# receiver.net
KiCad netlist of a schematic drawn in EAGLE
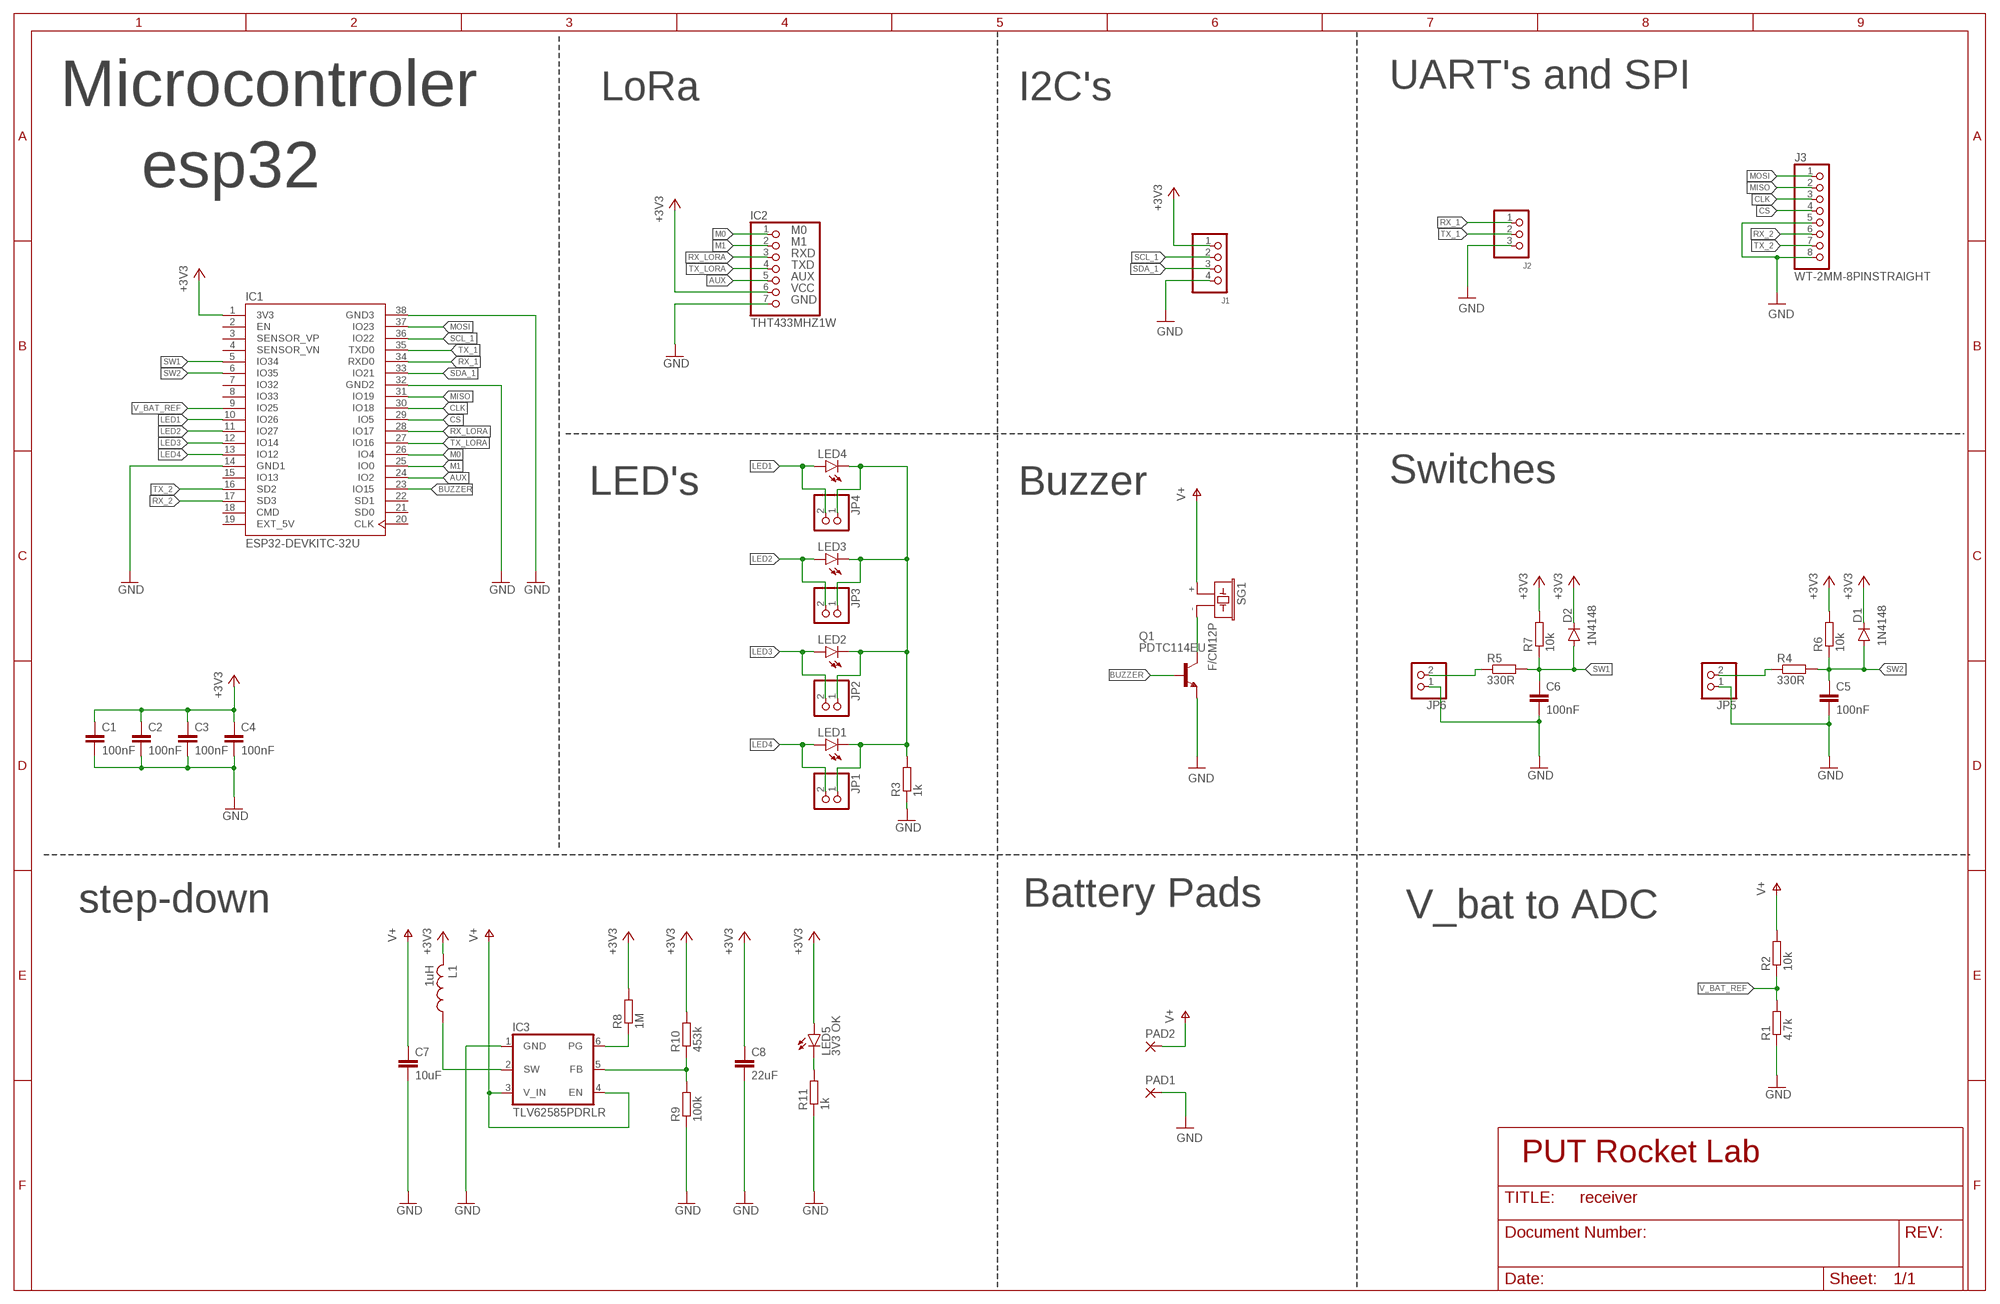
[diagram p0: schematic, sheet 1]

(export (version "E")
  (design (tool "Eeschema 10.0.6"))
  (components
    (comp (ref "C1")
      (value "100nF")
      (footprint "eagle-import:C0805")
      (libsource (lib "eagle-import") (part "C-EUC0805"))
    )
    (comp (ref "C2")
      (value "100nF")
      (footprint "eagle-import:C0805")
      (libsource (lib "eagle-import") (part "C-EUC0805"))
    )
    (comp (ref "C3")
      (value "100nF")
      (footprint "eagle-import:C0805")
      (libsource (lib "eagle-import") (part "C-EUC0805"))
    )
    (comp (ref "C4")
      (value "100nF")
      (footprint "eagle-import:C0805")
      (libsource (lib "eagle-import") (part "C-EUC0805"))
    )
    (comp (ref "C5")
      (value "100nF")
      (footprint "eagle-import:C0805")
      (libsource (lib "eagle-import") (part "rcl_334_C-EUC0805"))
    )
    (comp (ref "C6")
      (value "100nF")
      (footprint "eagle-import:C0805")
      (libsource (lib "eagle-import") (part "rcl_334_C-EUC0805"))
    )
    (comp (ref "C7")
      (value "10uF")
      (footprint "eagle-import:C0805")
      (libsource (lib "eagle-import") (part "C-EUC0805"))
    )
    (comp (ref "C8")
      (value "22uF")
      (footprint "eagle-import:C0805")
      (libsource (lib "eagle-import") (part "C-EUC0805"))
    )
    (comp (ref "D1")
      (value "1N4148")
      (footprint "eagle-import:SOD80C")
      (libsource (lib "eagle-import") (part "DIODE-SOD80C"))
    )
    (comp (ref "D2")
      (value "1N4148")
      (footprint "eagle-import:SOD80C")
      (libsource (lib "eagle-import") (part "DIODE-SOD80C"))
    )
    (comp (ref "IC1")
      (value "ESP32-DEVKITC-32U")
      (footprint "eagle-import:MODULE_ESP32-DEVKITC-32U")
      (fields (field (name "MF") "Espressif Systems"))
      (libsource (lib "eagle-import") (part "ESP32-DEVKITC-32U"))
    )
    (comp (ref "IC2")
      (value "THT433MHZ1W")
      (footprint "eagle-import:E32M1000")
      (libsource (lib "eagle-import") (part "THT433MHZ1W"))
    )
    (comp (ref "IC3")
      (value "TLV62585PDRLR")
      (footprint "eagle-import:SOT563")
      (libsource (lib "eagle-import") (part "TLV62585PDRLR"))
    )
    (comp (ref "J1")
      (value "WT-2MM-4PINSTRAIGHT")
      (footprint "eagle-import:W_TYPE_2MM_4_N")
      (libsource (lib "eagle-import") (part "WT-2MM-4PINSTRAIGHT"))
    )
    (comp (ref "J2")
      (value "WT-2MM-3PINSTRAIGHT")
      (footprint "eagle-import:W_TYPE_2MM_3_N")
      (libsource (lib "eagle-import") (part "WT-2MM-3PINSTRAIGHT"))
    )
    (comp (ref "J3")
      (value "WT-2MM-8PINSTRAIGHT")
      (footprint "eagle-import:W_TYPE_2MM_8_N")
      (libsource (lib "eagle-import") (part "WT-2MM-8PINSTRAIGHT"))
    )
    (comp (ref "JP1")
      (value "PINHD-1X2")
      (footprint "eagle-import:1X02")
      (libsource (lib "eagle-import") (part "PINHD-1X2"))
    )
    (comp (ref "JP2")
      (value "PINHD-1X2")
      (footprint "eagle-import:1X02")
      (libsource (lib "eagle-import") (part "PINHD-1X2"))
    )
    (comp (ref "JP3")
      (value "PINHD-1X2")
      (footprint "eagle-import:1X02")
      (libsource (lib "eagle-import") (part "PINHD-1X2"))
    )
    (comp (ref "JP4")
      (value "PINHD-1X2")
      (footprint "eagle-import:1X02")
      (libsource (lib "eagle-import") (part "PINHD-1X2"))
    )
    (comp (ref "JP5")
      (value "PINHD-1X2")
      (footprint "eagle-import:1X02")
      (libsource (lib "eagle-import") (part "PINHD-1X2"))
    )
    (comp (ref "JP6")
      (value "PINHD-1X2")
      (footprint "eagle-import:1X02")
      (libsource (lib "eagle-import") (part "PINHD-1X2"))
    )
    (comp (ref "L1")
      (value "1uH")
      (footprint "eagle-import:L5650M")
      (libsource (lib "eagle-import") (part "L-USL5650M"))
    )
    (comp (ref "LED1")
      (value "LEDCHIPLED_0805")
      (footprint "eagle-import:CHIPLED_0805")
      (libsource (lib "eagle-import") (part "LEDCHIPLED_0805"))
    )
    (comp (ref "LED2")
      (value "LEDCHIPLED_0805")
      (footprint "eagle-import:CHIPLED_0805")
      (libsource (lib "eagle-import") (part "LEDCHIPLED_0805"))
    )
    (comp (ref "LED3")
      (value "LEDCHIPLED_0805")
      (footprint "eagle-import:CHIPLED_0805")
      (libsource (lib "eagle-import") (part "LEDCHIPLED_0805"))
    )
    (comp (ref "LED4")
      (value "LEDCHIPLED_0805")
      (footprint "eagle-import:CHIPLED_0805")
      (libsource (lib "eagle-import") (part "LEDCHIPLED_0805"))
    )
    (comp (ref "LED5")
      (value "3V3 OK")
      (footprint "eagle-import:CHIPLED_0805")
      (libsource (lib "eagle-import") (part "LEDCHIPLED_0805"))
    )
    (comp (ref "PAD1")
      (value "WIREPAD2,54/1,1")
      (footprint "eagle-import:2,54_1,1")
      (libsource (lib "eagle-import") (part "WIREPAD2,54/1,1"))
    )
    (comp (ref "PAD2")
      (value "WIREPAD2,54/1,1")
      (footprint "eagle-import:2,54_1,1")
      (libsource (lib "eagle-import") (part "WIREPAD2,54/1,1"))
    )
    (comp (ref "Q1")
      (value "PDTC114EU")
      (footprint "eagle-import:SOT23")
      (libsource (lib "eagle-import") (part "BC846SMDA"))
    )
    (comp (ref "R1")
      (value "4.7k")
      (footprint "eagle-import:R0805")
      (libsource (lib "eagle-import") (part "R-EU_R0805"))
    )
    (comp (ref "R2")
      (value "10k")
      (footprint "eagle-import:R0805")
      (libsource (lib "eagle-import") (part "R-EU_R0805"))
    )
    (comp (ref "R3")
      (value "1k")
      (footprint "eagle-import:R0805")
      (libsource (lib "eagle-import") (part "R-EU_R0805"))
    )
    (comp (ref "R4")
      (value "330R")
      (footprint "eagle-import:R0805")
      (libsource (lib "eagle-import") (part "rcl_334_R-EU_R0805"))
    )
    (comp (ref "R5")
      (value "330R")
      (footprint "eagle-import:R0805")
      (libsource (lib "eagle-import") (part "rcl_334_R-EU_R0805"))
    )
    (comp (ref "R6")
      (value "10k")
      (footprint "eagle-import:R0805")
      (libsource (lib "eagle-import") (part "rcl_334_R-EU_R0805"))
    )
    (comp (ref "R7")
      (value "10k")
      (footprint "eagle-import:R0805")
      (libsource (lib "eagle-import") (part "rcl_334_R-EU_R0805"))
    )
    (comp (ref "R8")
      (value "1M")
      (footprint "eagle-import:R0805")
      (libsource (lib "eagle-import") (part "R-EU_R0805"))
    )
    (comp (ref "R9")
      (value "100k")
      (footprint "eagle-import:R0805")
      (libsource (lib "eagle-import") (part "R-EU_R0805"))
    )
    (comp (ref "R10")
      (value "453k")
      (footprint "eagle-import:R0805")
      (libsource (lib "eagle-import") (part "R-EU_R0805"))
    )
    (comp (ref "R11")
      (value "1k")
      (footprint "eagle-import:R0805")
      (libsource (lib "eagle-import") (part "R-EU_R0805"))
    )
    (comp (ref "SG1")
      (value "F/CM12P")
      (footprint "eagle-import:F_CM12P")
      (libsource (lib "eagle-import") (part "F/CM12P"))
    )
  )
  (nets
    (net (code "1") (name "+3V3") (class "Default")
      (node (ref "C1") (pin "1") (pinfunction "1_1") (pintype "passive"))
      (node (ref "C2") (pin "1") (pinfunction "1_1") (pintype "passive"))
      (node (ref "C3") (pin "1") (pinfunction "1_1") (pintype "passive"))
      (node (ref "C4") (pin "1") (pinfunction "1_1") (pintype "passive"))
      (node (ref "C8") (pin "1") (pinfunction "1_1") (pintype "passive"))
      (node (ref "D1") (pin "C") (pinfunction "C_C") (pintype "passive"))
      (node (ref "D2") (pin "C") (pinfunction "C_C") (pintype "passive"))
      (node (ref "IC1") (pin "1") (pinfunction "3V3_1") (pintype "power_in"))
      (node (ref "IC2") (pin "6") (pinfunction "VCC_6") (pintype "passive"))
      (node (ref "J1") (pin "1") (pinfunction "1_1") (pintype "passive"))
      (node (ref "L1") (pin "2") (pinfunction "2_2") (pintype "passive"))
      (node (ref "LED5") (pin "A") (pinfunction "A_A") (pintype "passive"))
      (node (ref "R10") (pin "2") (pinfunction "2_2") (pintype "passive"))
      (node (ref "R6") (pin "2") (pinfunction "2_2") (pintype "passive"))
      (node (ref "R7") (pin "2") (pinfunction "2_2") (pintype "passive"))
      (node (ref "R8") (pin "2") (pinfunction "2_2") (pintype "passive"))
    )
    (net (code "2") (name "/EXT_5V") (class "Default")
      (node (ref "IC1") (pin "19") (pinfunction "EXT_5V_19") (pintype "power_in"))
    )
    (net (code "3") (name "AUX") (class "Default")
      (node (ref "IC1") (pin "24") (pinfunction "IO2_24") (pintype "bidirectional"))
      (node (ref "IC2") (pin "5") (pinfunction "AUX_5") (pintype "passive"))
    )
    (net (code "4") (name "BUZZER") (class "Default")
      (node (ref "IC1") (pin "23") (pinfunction "IO15_23") (pintype "bidirectional"))
      (node (ref "Q1") (pin "1") (pinfunction "B_1") (pintype "passive"))
    )
    (net (code "5") (name "CLK") (class "Default")
      (node (ref "IC1") (pin "30") (pinfunction "IO18_30") (pintype "bidirectional"))
      (node (ref "J3") (pin "3") (pinfunction "3_3") (pintype "passive"))
    )
    (net (code "6") (name "CS") (class "Default")
      (node (ref "IC1") (pin "29") (pinfunction "IO5_29") (pintype "bidirectional"))
      (node (ref "J3") (pin "4") (pinfunction "4_4") (pintype "passive"))
    )
    (net (code "7") (name "GND") (class "Default")
      (node (ref "C1") (pin "2") (pinfunction "2_2") (pintype "passive"))
      (node (ref "C2") (pin "2") (pinfunction "2_2") (pintype "passive"))
      (node (ref "C3") (pin "2") (pinfunction "2_2") (pintype "passive"))
      (node (ref "C4") (pin "2") (pinfunction "2_2") (pintype "passive"))
      (node (ref "C5") (pin "2") (pinfunction "2_2") (pintype "passive"))
      (node (ref "C6") (pin "2") (pinfunction "2_2") (pintype "passive"))
      (node (ref "C7") (pin "2") (pinfunction "2_2") (pintype "passive"))
      (node (ref "C8") (pin "2") (pinfunction "2_2") (pintype "passive"))
      (node (ref "IC1") (pin "14") (pinfunction "GND1_14") (pintype "power_in"))
      (node (ref "IC1") (pin "32") (pinfunction "GND2_32") (pintype "power_in"))
      (node (ref "IC1") (pin "38") (pinfunction "GND3_38") (pintype "power_in"))
      (node (ref "IC2") (pin "7") (pinfunction "GND_7") (pintype "passive"))
      (node (ref "IC3") (pin "1") (pinfunction "GND_1") (pintype "input"))
      (node (ref "J1") (pin "4") (pinfunction "4_4") (pintype "passive"))
      (node (ref "J2") (pin "3") (pinfunction "3_3") (pintype "passive"))
      (node (ref "J3") (pin "5") (pinfunction "5_5") (pintype "passive"))
      (node (ref "J3") (pin "8") (pinfunction "8_8") (pintype "passive"))
      (node (ref "JP5") (pin "1") (pinfunction "1_1") (pintype "passive"))
      (node (ref "JP6") (pin "1") (pinfunction "1_1") (pintype "passive"))
      (node (ref "PAD1") (pin "1") (pinfunction "P_1") (pintype "passive"))
      (node (ref "Q1") (pin "2") (pinfunction "E_2") (pintype "passive"))
      (node (ref "R1") (pin "1") (pinfunction "1_1") (pintype "passive"))
      (node (ref "R11") (pin "1") (pinfunction "1_1") (pintype "passive"))
      (node (ref "R3") (pin "1") (pinfunction "1_1") (pintype "passive"))
      (node (ref "R9") (pin "1") (pinfunction "1_1") (pintype "passive"))
    )
    (net (code "8") (name "LED1") (class "Default")
      (node (ref "IC1") (pin "10") (pinfunction "IO26_10") (pintype "bidirectional"))
      (node (ref "JP4") (pin "2") (pinfunction "2_2") (pintype "passive"))
      (node (ref "LED4") (pin "A") (pinfunction "A_A") (pintype "passive"))
    )
    (net (code "9") (name "LED2") (class "Default")
      (node (ref "IC1") (pin "11") (pinfunction "IO27_11") (pintype "bidirectional"))
      (node (ref "JP3") (pin "2") (pinfunction "2_2") (pintype "passive"))
      (node (ref "LED3") (pin "A") (pinfunction "A_A") (pintype "passive"))
    )
    (net (code "10") (name "LED3") (class "Default")
      (node (ref "IC1") (pin "12") (pinfunction "IO14_12") (pintype "bidirectional"))
      (node (ref "JP2") (pin "2") (pinfunction "2_2") (pintype "passive"))
      (node (ref "LED2") (pin "A") (pinfunction "A_A") (pintype "passive"))
    )
    (net (code "11") (name "LED4") (class "Default")
      (node (ref "IC1") (pin "13") (pinfunction "IO12_13") (pintype "bidirectional"))
      (node (ref "JP1") (pin "2") (pinfunction "2_2") (pintype "passive"))
      (node (ref "LED1") (pin "A") (pinfunction "A_A") (pintype "passive"))
    )
    (net (code "12") (name "M0") (class "Default")
      (node (ref "IC1") (pin "26") (pinfunction "IO4_26") (pintype "bidirectional"))
      (node (ref "IC2") (pin "1") (pinfunction "M0_1") (pintype "passive"))
    )
    (net (code "13") (name "M1") (class "Default")
      (node (ref "IC1") (pin "25") (pinfunction "IO0_25") (pintype "bidirectional"))
      (node (ref "IC2") (pin "2") (pinfunction "M1_2") (pintype "passive"))
    )
    (net (code "14") (name "MISO") (class "Default")
      (node (ref "IC1") (pin "31") (pinfunction "IO19_31") (pintype "bidirectional"))
      (node (ref "J3") (pin "2") (pinfunction "2_2") (pintype "passive"))
    )
    (net (code "15") (name "MOSI") (class "Default")
      (node (ref "IC1") (pin "37") (pinfunction "IO23_37") (pintype "bidirectional"))
      (node (ref "J3") (pin "1") (pinfunction "1_1") (pintype "passive"))
    )
    (net (code "16") (name "Net-(IC3-FB)") (class "Default")
      (node (ref "IC3") (pin "5") (pinfunction "FB_5") (pintype "input"))
      (node (ref "R10") (pin "1") (pinfunction "1_1") (pintype "passive"))
      (node (ref "R9") (pin "2") (pinfunction "2_2") (pintype "passive"))
    )
    (net (code "17") (name "Net-(IC3-PG)") (class "Default")
      (node (ref "IC3") (pin "6") (pinfunction "PG_6") (pintype "output"))
      (node (ref "R8") (pin "1") (pinfunction "1_1") (pintype "passive"))
    )
    (net (code "18") (name "Net-(IC3-SW)") (class "Default")
      (node (ref "IC3") (pin "2") (pinfunction "SW_2") (pintype "input"))
      (node (ref "L1") (pin "1") (pinfunction "1_1") (pintype "passive"))
    )
    (net (code "19") (name "Net-(JP1-Pad1)") (class "Default")
      (node (ref "JP1") (pin "1") (pinfunction "1_1") (pintype "passive"))
      (node (ref "JP2") (pin "1") (pinfunction "1_1") (pintype "passive"))
      (node (ref "JP3") (pin "1") (pinfunction "1_1") (pintype "passive"))
      (node (ref "JP4") (pin "1") (pinfunction "1_1") (pintype "passive"))
      (node (ref "LED1") (pin "C") (pinfunction "C_C") (pintype "passive"))
      (node (ref "LED2") (pin "C") (pinfunction "C_C") (pintype "passive"))
      (node (ref "LED3") (pin "C") (pinfunction "C_C") (pintype "passive"))
      (node (ref "LED4") (pin "C") (pinfunction "C_C") (pintype "passive"))
      (node (ref "R3") (pin "2") (pinfunction "2_2") (pintype "passive"))
    )
    (net (code "20") (name "Net-(JP5-Pad2)") (class "Default")
      (node (ref "JP5") (pin "2") (pinfunction "2_2") (pintype "passive"))
      (node (ref "R4") (pin "1") (pinfunction "1_1") (pintype "passive"))
    )
    (net (code "21") (name "Net-(JP6-Pad2)") (class "Default")
      (node (ref "JP6") (pin "2") (pinfunction "2_2") (pintype "passive"))
      (node (ref "R5") (pin "1") (pinfunction "1_1") (pintype "passive"))
    )
    (net (code "22") (name "Net-(LED5-PadC)") (class "Default")
      (node (ref "LED5") (pin "C") (pinfunction "C_C") (pintype "passive"))
      (node (ref "R11") (pin "2") (pinfunction "2_2") (pintype "passive"))
    )
    (net (code "23") (name "Net-(Q1-C)") (class "Default")
      (node (ref "Q1") (pin "3") (pinfunction "C_3") (pintype "passive"))
      (node (ref "SG1") (pin "-") (pinfunction "2_-") (pintype "passive"))
    )
    (net (code "24") (name "RX_1") (class "Default")
      (node (ref "IC1") (pin "34") (pinfunction "RXD0_34") (pintype "input"))
      (node (ref "J2") (pin "1") (pinfunction "1_1") (pintype "passive"))
    )
    (net (code "25") (name "RX_2") (class "Default")
      (node (ref "IC1") (pin "17") (pinfunction "SD3_17") (pintype "bidirectional"))
      (node (ref "J3") (pin "6") (pinfunction "6_6") (pintype "passive"))
    )
    (net (code "26") (name "RX_LORA") (class "Default")
      (node (ref "IC1") (pin "28") (pinfunction "IO17_28") (pintype "bidirectional"))
      (node (ref "IC2") (pin "3") (pinfunction "RXD_3") (pintype "passive"))
    )
    (net (code "27") (name "SCL_1") (class "Default")
      (node (ref "IC1") (pin "36") (pinfunction "IO22_36") (pintype "bidirectional"))
      (node (ref "J1") (pin "2") (pinfunction "2_2") (pintype "passive"))
    )
    (net (code "28") (name "SDA_1") (class "Default")
      (node (ref "IC1") (pin "33") (pinfunction "IO21_33") (pintype "bidirectional"))
      (node (ref "J1") (pin "3") (pinfunction "3_3") (pintype "passive"))
    )
    (net (code "29") (name "SW1") (class "Default")
      (node (ref "C6") (pin "1") (pinfunction "1_1") (pintype "passive"))
      (node (ref "D2") (pin "A") (pinfunction "A_A") (pintype "passive"))
      (node (ref "IC1") (pin "5") (pinfunction "IO34_5") (pintype "bidirectional"))
      (node (ref "R5") (pin "2") (pinfunction "2_2") (pintype "passive"))
      (node (ref "R7") (pin "1") (pinfunction "1_1") (pintype "passive"))
    )
    (net (code "30") (name "SW2") (class "Default")
      (node (ref "C5") (pin "1") (pinfunction "1_1") (pintype "passive"))
      (node (ref "D1") (pin "A") (pinfunction "A_A") (pintype "passive"))
      (node (ref "IC1") (pin "6") (pinfunction "IO35_6") (pintype "bidirectional"))
      (node (ref "R4") (pin "2") (pinfunction "2_2") (pintype "passive"))
      (node (ref "R6") (pin "1") (pinfunction "1_1") (pintype "passive"))
    )
    (net (code "31") (name "TX_1") (class "Default")
      (node (ref "IC1") (pin "35") (pinfunction "TXD0_35") (pintype "output"))
      (node (ref "J2") (pin "2") (pinfunction "2_2") (pintype "passive"))
    )
    (net (code "32") (name "TX_2") (class "Default")
      (node (ref "IC1") (pin "16") (pinfunction "SD2_16") (pintype "bidirectional"))
      (node (ref "J3") (pin "7") (pinfunction "7_7") (pintype "passive"))
    )
    (net (code "33") (name "TX_LORA") (class "Default")
      (node (ref "IC1") (pin "27") (pinfunction "IO16_27") (pintype "bidirectional"))
      (node (ref "IC2") (pin "4") (pinfunction "TXD_4") (pintype "passive"))
    )
    (net (code "34") (name "V+") (class "Default")
      (node (ref "C7") (pin "1") (pinfunction "1_1") (pintype "passive"))
      (node (ref "IC3") (pin "3") (pinfunction "V_IN_3") (pintype "input"))
      (node (ref "IC3") (pin "4") (pinfunction "EN_4") (pintype "input"))
      (node (ref "PAD2") (pin "1") (pinfunction "P_1") (pintype "passive"))
      (node (ref "R2") (pin "2") (pinfunction "2_2") (pintype "passive"))
      (node (ref "SG1") (pin "+") (pinfunction "1_+") (pintype "passive"))
    )
    (net (code "35") (name "V_BAT_REF") (class "Default")
      (node (ref "IC1") (pin "9") (pinfunction "IO25_9") (pintype "bidirectional"))
      (node (ref "R1") (pin "2") (pinfunction "2_2") (pintype "passive"))
      (node (ref "R2") (pin "1") (pinfunction "1_1") (pintype "passive"))
    )
    (net (code "36") (name "unconnected-(IC1-CLK-Pad20)") (class "Default")
      (node (ref "IC1") (pin "20") (pinfunction "CLK_20") (pintype "input"))
    )
    (net (code "37") (name "unconnected-(IC1-CMD-Pad18)") (class "Default")
      (node (ref "IC1") (pin "18") (pinfunction "CMD_18") (pintype "bidirectional"))
    )
    (net (code "38") (name "unconnected-(IC1-EN-Pad2)") (class "Default")
      (node (ref "IC1") (pin "2") (pinfunction "EN_2") (pintype "input"))
    )
    (net (code "39") (name "unconnected-(IC1-IO13-Pad15)") (class "Default")
      (node (ref "IC1") (pin "15") (pinfunction "IO13_15") (pintype "bidirectional"))
    )
    (net (code "40") (name "unconnected-(IC1-IO32-Pad7)") (class "Default")
      (node (ref "IC1") (pin "7") (pinfunction "IO32_7") (pintype "bidirectional"))
    )
    (net (code "41") (name "unconnected-(IC1-IO33-Pad8)") (class "Default")
      (node (ref "IC1") (pin "8") (pinfunction "IO33_8") (pintype "bidirectional"))
    )
    (net (code "42") (name "unconnected-(IC1-SD0-Pad21)") (class "Default")
      (node (ref "IC1") (pin "21") (pinfunction "SD0_21") (pintype "bidirectional"))
    )
    (net (code "43") (name "unconnected-(IC1-SD1-Pad22)") (class "Default")
      (node (ref "IC1") (pin "22") (pinfunction "SD1_22") (pintype "bidirectional"))
    )
    (net (code "44") (name "unconnected-(IC1-SENSOR_VN-Pad4)") (class "Default")
      (node (ref "IC1") (pin "4") (pinfunction "SENSOR_VN_4") (pintype "input"))
    )
    (net (code "45") (name "unconnected-(IC1-SENSOR_VP-Pad3)") (class "Default")
      (node (ref "IC1") (pin "3") (pinfunction "SENSOR_VP_3") (pintype "input"))
    )
  )
)
